# Main.net
KiCad netlist of a schematic drawn in Altium Designer
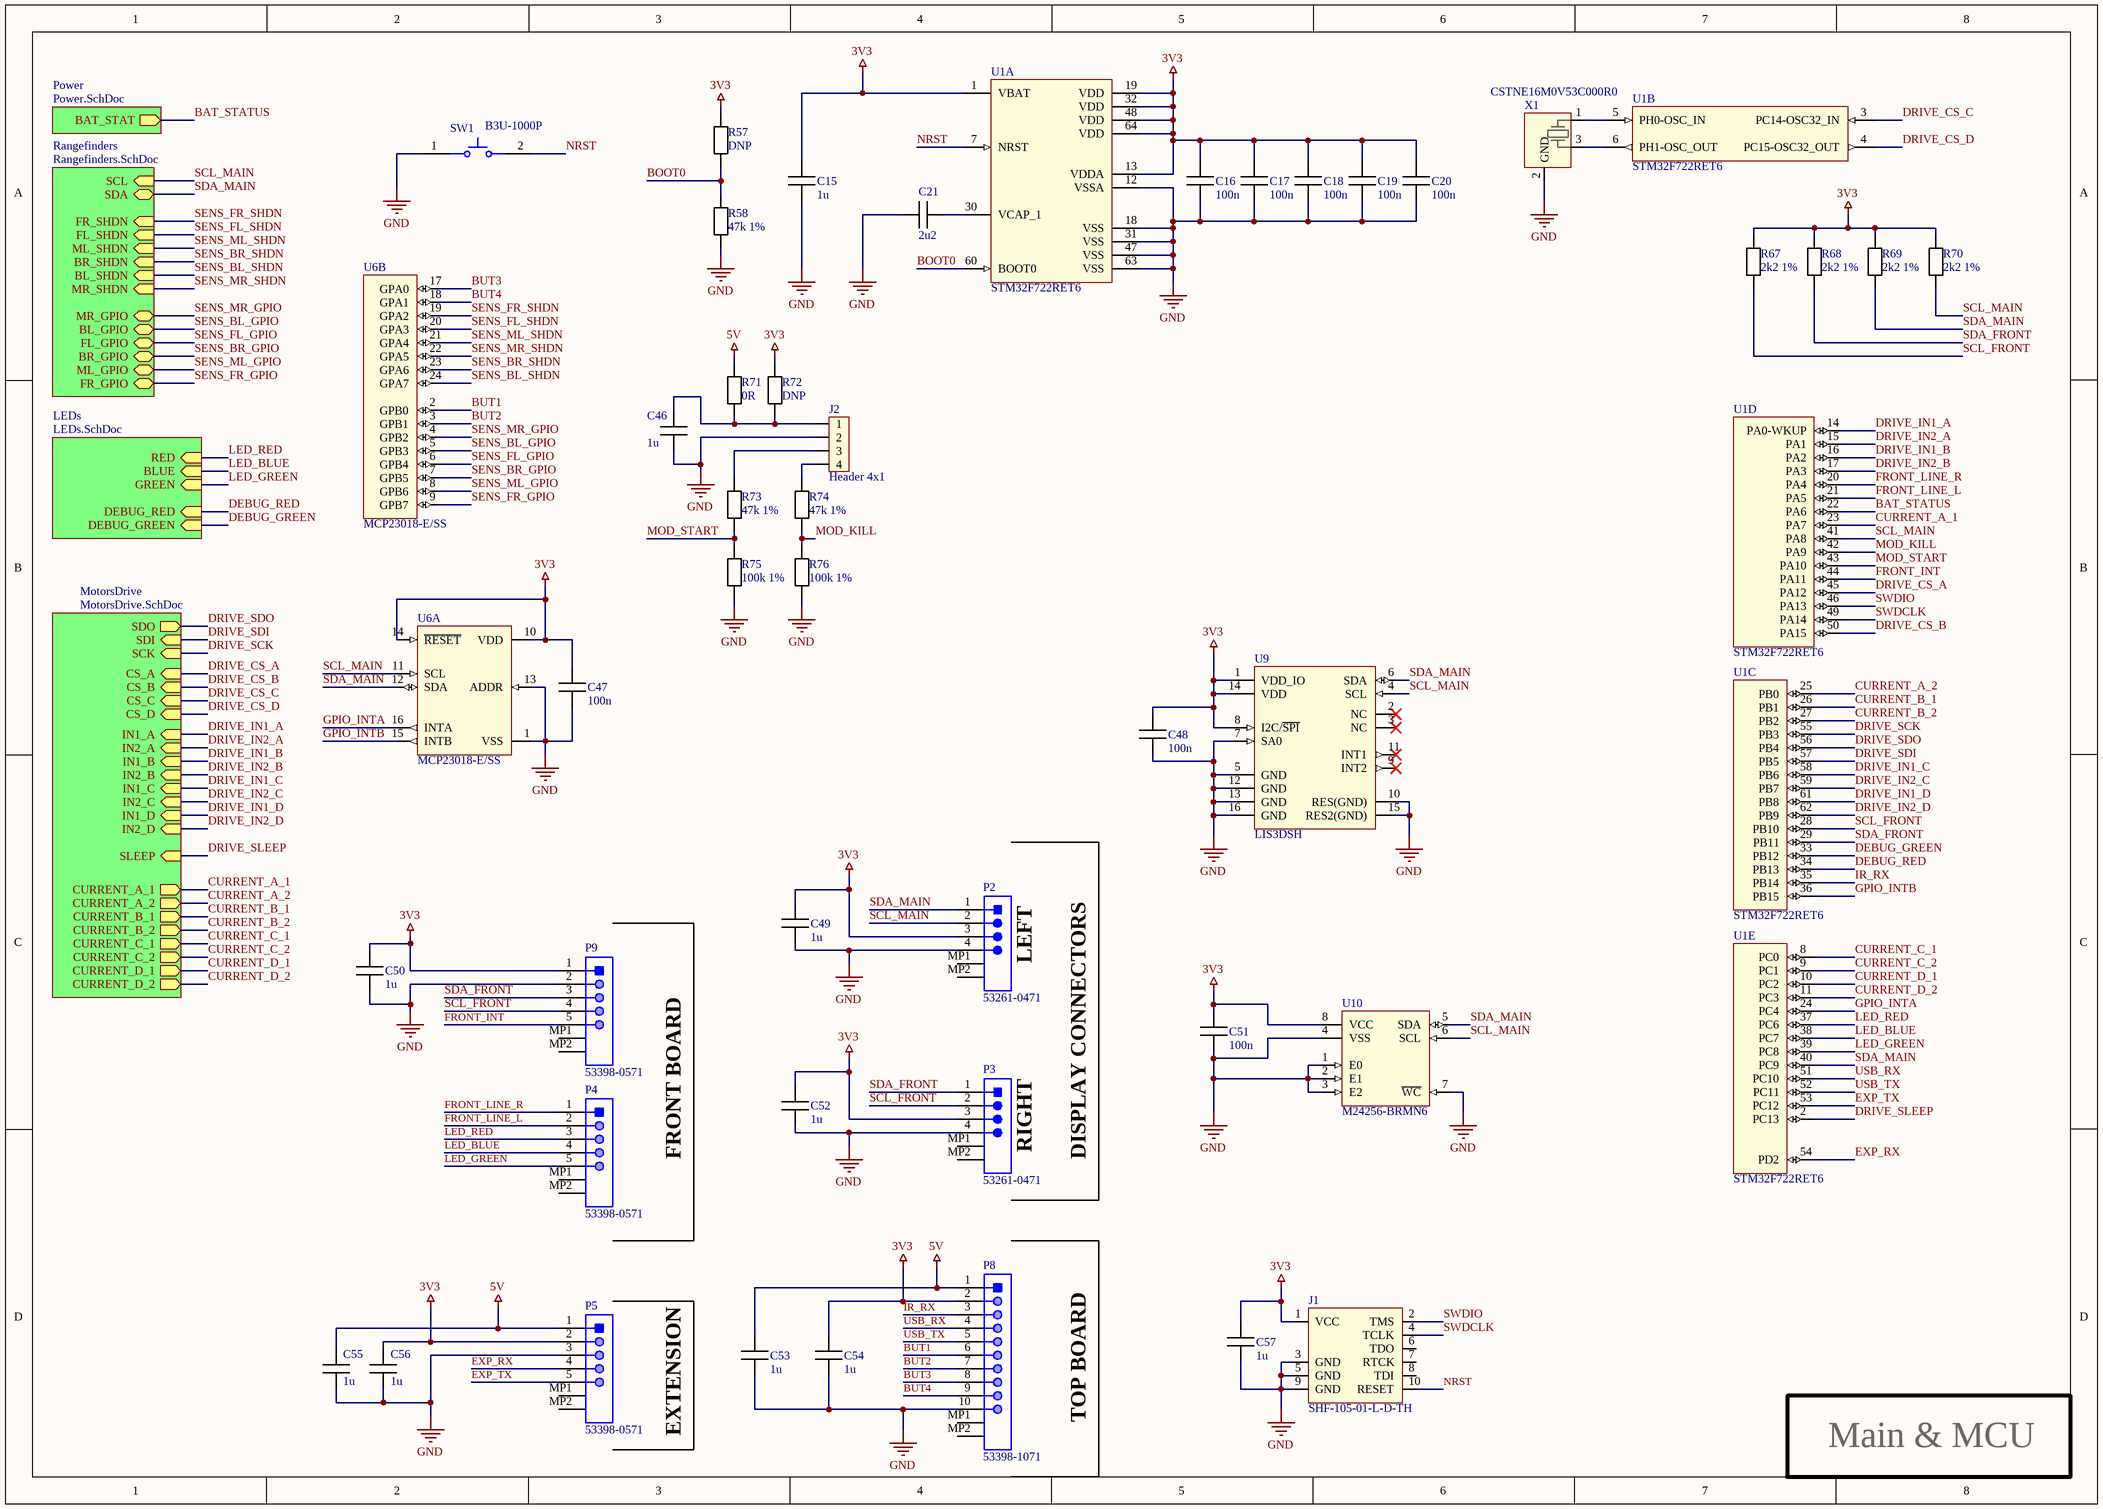
[diagram p0: Main.SchDoc]

(export (version "E")
  (design (tool "Eeschema 10.0.6"))
  (components
    (comp (ref "C15")
      (value "1u")
      (footprint "C_0603_AUTO")
      (fields (field (name "MANUFACTURER") "[Generic]"))
      (libsource (lib "GuowLib") (part "Capacitor"))
    )
    (comp (ref "C16")
      (value "100n")
      (footprint "C_0603_AUTO")
      (fields (field (name "MANUFACTURER") "[Generic]"))
      (libsource (lib "GuowLib") (part "Capacitor"))
    )
    (comp (ref "C17")
      (value "100n")
      (footprint "C_0603_AUTO")
      (fields (field (name "MANUFACTURER") "[Generic]"))
      (libsource (lib "GuowLib") (part "Capacitor"))
    )
    (comp (ref "C18")
      (value "100n")
      (footprint "C_0603_AUTO")
      (fields (field (name "MANUFACTURER") "[Generic]"))
      (libsource (lib "GuowLib") (part "Capacitor"))
    )
    (comp (ref "C19")
      (value "100n")
      (footprint "C_0603_AUTO")
      (fields (field (name "MANUFACTURER") "[Generic]"))
      (libsource (lib "GuowLib") (part "Capacitor"))
    )
    (comp (ref "C20")
      (value "100n")
      (footprint "C_0603_AUTO")
      (fields (field (name "MANUFACTURER") "[Generic]"))
      (libsource (lib "GuowLib") (part "Capacitor"))
    )
    (comp (ref "C21")
      (value "2u2")
      (footprint "C_0603_AUTO")
      (fields (field (name "MANUFACTURER") "[Generic]"))
      (libsource (lib "GuowLib") (part "Capacitor"))
    )
    (comp (ref "C46")
      (value "1u")
      (footprint "C_0603_AUTO")
      (fields (field (name "MANUFACTURER") "[Generic]"))
      (libsource (lib "GuowLib") (part "Capacitor"))
    )
    (comp (ref "C47")
      (value "100n")
      (footprint "C_0603_AUTO")
      (fields (field (name "MANUFACTURER") "[Generic]"))
      (libsource (lib "GuowLib") (part "Capacitor"))
    )
    (comp (ref "C48")
      (value "100n")
      (footprint "C_0603_AUTO")
      (fields (field (name "MANUFACTURER") "[Generic]"))
      (libsource (lib "GuowLib") (part "Capacitor"))
    )
    (comp (ref "C49")
      (value "1u")
      (footprint "C_0603_AUTO")
      (fields (field (name "MANUFACTURER") "[Generic]"))
      (libsource (lib "GuowLib") (part "Capacitor"))
    )
    (comp (ref "C50")
      (value "1u")
      (footprint "C_0603_AUTO")
      (fields (field (name "MANUFACTURER") "[Generic]"))
      (libsource (lib "GuowLib") (part "Capacitor"))
    )
    (comp (ref "C51")
      (value "100n")
      (footprint "C_0603_AUTO")
      (fields (field (name "MANUFACTURER") "[Generic]"))
      (libsource (lib "GuowLib") (part "Capacitor"))
    )
    (comp (ref "C52")
      (value "1u")
      (footprint "C_0603_AUTO")
      (fields (field (name "MANUFACTURER") "[Generic]"))
      (libsource (lib "GuowLib") (part "Capacitor"))
    )
    (comp (ref "C53")
      (value "1u")
      (footprint "C_0603_AUTO")
      (fields (field (name "MANUFACTURER") "[Generic]"))
      (libsource (lib "GuowLib") (part "Capacitor"))
    )
    (comp (ref "C54")
      (value "1u")
      (footprint "C_0603_AUTO")
      (fields (field (name "MANUFACTURER") "[Generic]"))
      (libsource (lib "GuowLib") (part "Capacitor"))
    )
    (comp (ref "C55")
      (value "1u")
      (footprint "C_0603_AUTO")
      (fields (field (name "MANUFACTURER") "[Generic]"))
      (libsource (lib "GuowLib") (part "Capacitor"))
    )
    (comp (ref "C56")
      (value "1u")
      (footprint "C_0603_AUTO")
      (fields (field (name "MANUFACTURER") "[Generic]"))
      (libsource (lib "GuowLib") (part "Capacitor"))
    )
    (comp (ref "C57")
      (value "1u")
      (footprint "C_0603_AUTO")
      (fields (field (name "MANUFACTURER") "[Generic]"))
      (libsource (lib "GuowLib") (part "Capacitor"))
    )
    (comp (ref "J1")
      (value "SHF-105-01-L-D-TH")
      (footprint "SHF-105-01-L-D-TH")
      (description "Standard ARM 20 pin JTAG connector. Angle 90 deg.")
      (fields (field (name "MANUFACTURER") "Samtec"))
      (libsource (lib "GuowLib") (part "JTAG_ARM_MINI_10_PIN"))
    )
    (comp (ref "J2")
      (value "Header 4x1")
      (footprint "F_4X1_254")
      (fields (field (name "MANUFACTURER") "NA"))
      (libsource (lib "GuowLib") (part "Header 4x1"))
    )
    (comp (ref "P2")
      (value "53261-0471")
      (footprint "MOLEX-53261-0471_V")
      (description "Male Header, Pitch 1.25 mm, 1 x 4 Position, Height 3.4 mm, -40 to 85 degC, RoHS, Tape and Reel")
      (fields (field (name "MANUFACTURER") "Molex"))
      (libsource (lib "Altium Content Vault") (part "CN-1P-2M-R4_A"))
    )
    (comp (ref "P3")
      (value "53261-0471")
      (footprint "MOLEX-53261-0471_V")
      (description "Male Header, Pitch 1.25 mm, 1 x 4 Position, Height 3.4 mm, -40 to 85 degC, RoHS, Tape and Reel")
      (fields (field (name "MANUFACTURER") "Molex"))
      (libsource (lib "Altium Content Vault") (part "CN-1P-2M-R4_A"))
    )
    (comp (ref "P4")
      (value "53398-0571")
      (footprint "MOLX-53398-0571-5_V")
      (description "Male Header, Pitch 1.25 mm, 1 x 5 Postion, Height 4.7 mm, -40 to 85 degC, RoHS, Tape and Reel")
      (fields (field (name "MANUFACTURER") "Molex"))
      (libsource (lib "Altium Content Vault") (part "CN-1P-2M-R5"))
    )
    (comp (ref "P5")
      (value "53398-0571")
      (footprint "MOLX-53398-0571-5_V")
      (description "Male Header, Pitch 1.25 mm, 1 x 5 Postion, Height 4.7 mm, -40 to 85 degC, RoHS, Tape and Reel")
      (fields (field (name "MANUFACTURER") "Molex"))
      (libsource (lib "Altium Content Vault") (part "CN-1P-2M-R5"))
    )
    (comp (ref "P8")
      (value "53398-1071")
      (footprint "MOLX-53398-1071_V")
      (description "Male Header, Pitch 1.25 mm, 1 x 10 Position, Height 4.7 mm, -40 to 85 degC, RoHS, Tape and Reel")
      (fields (field (name "MANUFACTURER") "Molex"))
      (libsource (lib "Altium Content Vault") (part "CN-1P-2M-R10"))
    )
    (comp (ref "P9")
      (value "53398-0571")
      (footprint "MOLX-53398-0571-5_V")
      (description "Male Header, Pitch 1.25 mm, 1 x 5 Postion, Height 4.7 mm, -40 to 85 degC, RoHS, Tape and Reel")
      (fields (field (name "MANUFACTURER") "Molex"))
      (libsource (lib "Altium Content Vault") (part "CN-1P-2M-R5"))
    )
    (comp (ref "R57")
      (value "DNP")
      (footprint "R_0603_AUTO")
      (fields (field (name "MPN") "[Generic]"))
      (libsource (lib "GuowLib") (part "Resistor"))
    )
    (comp (ref "R58")
      (value "47k 1%")
      (footprint "R_0603_AUTO")
      (fields (field (name "MPN") "[Generic]"))
      (libsource (lib "GuowLib") (part "Resistor"))
    )
    (comp (ref "R67")
      (value "2k2 1%")
      (footprint "R_0603_AUTO")
      (fields (field (name "MPN") "[Generic]"))
      (libsource (lib "GuowLib") (part "Resistor"))
    )
    (comp (ref "R68")
      (value "2k2 1%")
      (footprint "R_0603_AUTO")
      (fields (field (name "MPN") "[Generic]"))
      (libsource (lib "GuowLib") (part "Resistor"))
    )
    (comp (ref "R69")
      (value "2k2 1%")
      (footprint "R_0603_AUTO")
      (fields (field (name "MPN") "[Generic]"))
      (libsource (lib "GuowLib") (part "Resistor"))
    )
    (comp (ref "R70")
      (value "2k2 1%")
      (footprint "R_0603_AUTO")
      (fields (field (name "MPN") "[Generic]"))
      (libsource (lib "GuowLib") (part "Resistor"))
    )
    (comp (ref "R71")
      (value "0R")
      (footprint "R_0603_AUTO")
      (fields (field (name "MPN") "[Generic]"))
      (libsource (lib "GuowLib") (part "Resistor"))
    )
    (comp (ref "R72")
      (value "DNP")
      (footprint "R_0603_AUTO")
      (fields (field (name "MPN") "[Generic]"))
      (libsource (lib "GuowLib") (part "Resistor"))
    )
    (comp (ref "R73")
      (value "47k 1%")
      (footprint "R_0603_AUTO")
      (fields (field (name "MPN") "[Generic]"))
      (libsource (lib "GuowLib") (part "Resistor"))
    )
    (comp (ref "R74")
      (value "47k 1%")
      (footprint "R_0603_AUTO")
      (fields (field (name "MPN") "[Generic]"))
      (libsource (lib "GuowLib") (part "Resistor"))
    )
    (comp (ref "R75")
      (value "100k 1%")
      (footprint "R_0603_AUTO")
      (fields (field (name "MPN") "[Generic]"))
      (libsource (lib "GuowLib") (part "Resistor"))
    )
    (comp (ref "R76")
      (value "100k 1%")
      (footprint "R_0603_AUTO")
      (fields (field (name "MPN") "[Generic]"))
      (libsource (lib "GuowLib") (part "Resistor"))
    )
    (comp (ref "SW1")
      (value "B3U-1000P")
      (footprint "OMRON-B3U-1000_V")
      (description "Ultra-Small Tactile Switch, 0.05 A, 12 V, -25 to 70 degC, 2-Pin SMD, RoHS, Tape and Reel")
      (fields (field (name "MANUFACTURER") "Omron Electronic Components"))
      (libsource (lib "Altium Content Vault") (part "SW-SPST-NO-2"))
    )
    (comp (ref "U1")
      (value "STM32F722RET6")
      (footprint "LQFP_64_HAND")
      (description "ST 32-bit MCU, 64-pin package")
      (fields (field (name "MANUFACTURER") "STMicroelectronics"))
      (libsource (lib "GuowLib") (part "STM32F722RET6"))
    )
    (comp (ref "U6")
      (value "MCP23018-E/SS")
      (footprint "SSOP-24_HAND")
      (description "Expander I/O, 16-bit, 3.4 MHz, I2C, 1.8 V, 5.5 V, SSOP24")
      (fields (field (name "MANUFACTURER") "Microchip"))
      (libsource (lib "GuowLib") (part "MCP23018-E/SS"))
    )
    (comp (ref "U9")
      (value "LIS3DSH")
      (footprint "LGA16_AUTO")
      (fields (field (name "MANUFACTURER") "STMicroelectronics"))
      (libsource (lib "GuowLib") (part "LIS3DSH"))
    )
    (comp (ref "U10")
      (value "M24256-BRMN6")
      (footprint "SOIC_8_AUTO")
      (description "256 Kbit Serial I2C Bus EEPROM")
      (fields (field (name "MANUFACTURER") "STMicroelectronics"))
      (libsource (lib "GuowLib") (part "M24256-BRMN6"))
    )
    (comp (ref "X1")
      (value "CSTNE16M0V53C000R0")
      (footprint "Murata_CSTCE")
      (description "16MHz crystal resonator")
      (fields (field (name "MANUFACTURER") "Murata"))
      (libsource (lib "GuowLib") (part "CSTNE16M0V53C000R0"))
    )
  )
  (nets
    (net (code "1") (name "/BAT_STATUS") (class "Default")
      (node (ref "U1") (pin "22") (pinfunction "PA6_22") (pintype "bidirectional"))
    )
    (net (code "2") (name "/BOOT0") (class "Default")
      (node (ref "R57") (pin "1") (pinfunction "1_1") (pintype "passive"))
      (node (ref "R58") (pin "2") (pinfunction "2_2") (pintype "passive"))
      (node (ref "U1") (pin "60") (pinfunction "BOOT0_60") (pintype "input"))
    )
    (net (code "3") (name "/BUT1") (class "Default")
      (node (ref "P8") (pin "6") (pinfunction "6_6") (pintype "passive"))
      (node (ref "U6") (pin "2") (pinfunction "GPB0_2") (pintype "bidirectional"))
    )
    (net (code "4") (name "/BUT2") (class "Default")
      (node (ref "P8") (pin "7") (pinfunction "7_7") (pintype "passive"))
      (node (ref "U6") (pin "3") (pinfunction "GPB1_3") (pintype "bidirectional"))
    )
    (net (code "5") (name "/BUT3") (class "Default")
      (node (ref "P8") (pin "8") (pinfunction "8_8") (pintype "passive"))
      (node (ref "U6") (pin "17") (pinfunction "GPA0_17") (pintype "bidirectional"))
    )
    (net (code "6") (name "/BUT4") (class "Default")
      (node (ref "P8") (pin "9") (pinfunction "9_9") (pintype "passive"))
      (node (ref "U6") (pin "18") (pinfunction "GPA1_18") (pintype "bidirectional"))
    )
    (net (code "7") (name "/CURRENT_A_1") (class "Default")
      (node (ref "U1") (pin "23") (pinfunction "PA7_23") (pintype "bidirectional"))
    )
    (net (code "8") (name "/CURRENT_A_2") (class "Default")
      (node (ref "U1") (pin "25") (pinfunction "PB0_25") (pintype "bidirectional"))
    )
    (net (code "9") (name "/CURRENT_B_1") (class "Default")
      (node (ref "U1") (pin "26") (pinfunction "PB1_26") (pintype "bidirectional"))
    )
    (net (code "10") (name "/CURRENT_B_2") (class "Default")
      (node (ref "U1") (pin "27") (pinfunction "PB2_27") (pintype "bidirectional"))
    )
    (net (code "11") (name "/CURRENT_C_1") (class "Default")
      (node (ref "U1") (pin "8") (pinfunction "PC0_8") (pintype "bidirectional"))
    )
    (net (code "12") (name "/CURRENT_C_2") (class "Default")
      (node (ref "U1") (pin "9") (pinfunction "PC1_9") (pintype "bidirectional"))
    )
    (net (code "13") (name "/CURRENT_D_1") (class "Default")
      (node (ref "U1") (pin "10") (pinfunction "PC2_10") (pintype "bidirectional"))
    )
    (net (code "14") (name "/CURRENT_D_2") (class "Default")
      (node (ref "U1") (pin "11") (pinfunction "PC3_11") (pintype "bidirectional"))
    )
    (net (code "15") (name "/DEBUG_GREEN") (class "Default")
      (node (ref "U1") (pin "33") (pinfunction "PB12_33") (pintype "bidirectional"))
    )
    (net (code "16") (name "/DEBUG_RED") (class "Default")
      (node (ref "U1") (pin "34") (pinfunction "PB13_34") (pintype "bidirectional"))
    )
    (net (code "17") (name "/DRIVE_CS_A") (class "Default")
      (node (ref "U1") (pin "45") (pinfunction "PA12_45") (pintype "bidirectional"))
    )
    (net (code "18") (name "/DRIVE_CS_B") (class "Default")
      (node (ref "U1") (pin "50") (pinfunction "PA15_50") (pintype "bidirectional"))
    )
    (net (code "19") (name "/DRIVE_CS_C") (class "Default")
      (node (ref "U1") (pin "3") (pinfunction "PC14-OSC32_IN_3") (pintype "input"))
    )
    (net (code "20") (name "/DRIVE_CS_D") (class "Default")
      (node (ref "U1") (pin "4") (pinfunction "PC15-OSC32_OUT_4") (pintype "output"))
    )
    (net (code "21") (name "/DRIVE_IN1_A") (class "Default")
      (node (ref "U1") (pin "14") (pinfunction "PA0-WKUP_14") (pintype "bidirectional"))
    )
    (net (code "22") (name "/DRIVE_IN1_B") (class "Default")
      (node (ref "U1") (pin "16") (pinfunction "PA2_16") (pintype "bidirectional"))
    )
    (net (code "23") (name "/DRIVE_IN1_C") (class "Default")
      (node (ref "U1") (pin "58") (pinfunction "PB6_58") (pintype "bidirectional"))
    )
    (net (code "24") (name "/DRIVE_IN1_D") (class "Default")
      (node (ref "U1") (pin "61") (pinfunction "PB8_61") (pintype "bidirectional"))
    )
    (net (code "25") (name "/DRIVE_IN2_A") (class "Default")
      (node (ref "U1") (pin "15") (pinfunction "PA1_15") (pintype "bidirectional"))
    )
    (net (code "26") (name "/DRIVE_IN2_B") (class "Default")
      (node (ref "U1") (pin "17") (pinfunction "PA3_17") (pintype "bidirectional"))
    )
    (net (code "27") (name "/DRIVE_IN2_C") (class "Default")
      (node (ref "U1") (pin "59") (pinfunction "PB7_59") (pintype "bidirectional"))
    )
    (net (code "28") (name "/DRIVE_IN2_D") (class "Default")
      (node (ref "U1") (pin "62") (pinfunction "PB9_62") (pintype "bidirectional"))
    )
    (net (code "29") (name "/DRIVE_SCK") (class "Default")
      (node (ref "U1") (pin "55") (pinfunction "PB3_55") (pintype "bidirectional"))
    )
    (net (code "30") (name "/DRIVE_SDI") (class "Default")
      (node (ref "U1") (pin "57") (pinfunction "PB5_57") (pintype "bidirectional"))
    )
    (net (code "31") (name "/DRIVE_SDO") (class "Default")
      (node (ref "U1") (pin "56") (pinfunction "PB4_56") (pintype "bidirectional"))
    )
    (net (code "32") (name "/DRIVE_SLEEP") (class "Default")
      (node (ref "U1") (pin "2") (pinfunction "PC13_2") (pintype "bidirectional"))
    )
    (net (code "33") (name "/EXP_RX") (class "Default")
      (node (ref "P5") (pin "4") (pinfunction "4_4") (pintype "passive"))
      (node (ref "U1") (pin "54") (pinfunction "PD2_54") (pintype "bidirectional"))
    )
    (net (code "34") (name "/EXP_TX") (class "Default")
      (node (ref "P5") (pin "5") (pinfunction "5_5") (pintype "passive"))
      (node (ref "U1") (pin "53") (pinfunction "PC12_53") (pintype "bidirectional"))
    )
    (net (code "35") (name "/FRONT_INT") (class "Default")
      (node (ref "P9") (pin "5") (pinfunction "5_5") (pintype "passive"))
      (node (ref "U1") (pin "44") (pinfunction "PA11_44") (pintype "bidirectional"))
    )
    (net (code "36") (name "/FRONT_LINE_L") (class "Default")
      (node (ref "P4") (pin "2") (pinfunction "2_2") (pintype "passive"))
      (node (ref "U1") (pin "21") (pinfunction "PA5_21") (pintype "bidirectional"))
    )
    (net (code "37") (name "/FRONT_LINE_R") (class "Default")
      (node (ref "P4") (pin "1") (pinfunction "1_1") (pintype "passive"))
      (node (ref "U1") (pin "20") (pinfunction "PA4_20") (pintype "bidirectional"))
    )
    (net (code "38") (name "/GPIO_INTA") (class "Default")
      (node (ref "U1") (pin "24") (pinfunction "PC4_24") (pintype "bidirectional"))
      (node (ref "U6") (pin "16") (pinfunction "INTA_16") (pintype "output"))
    )
    (net (code "39") (name "/GPIO_INTB") (class "Default")
      (node (ref "U1") (pin "36") (pinfunction "PB15_36") (pintype "bidirectional"))
      (node (ref "U6") (pin "15") (pinfunction "INTB_15") (pintype "output"))
    )
    (net (code "40") (name "/IR_RX") (class "Default")
      (node (ref "P8") (pin "3") (pinfunction "3_3") (pintype "passive"))
      (node (ref "U1") (pin "35") (pinfunction "PB14_35") (pintype "bidirectional"))
    )
    (net (code "41") (name "/LED_BLUE") (class "Default")
      (node (ref "P4") (pin "4") (pinfunction "4_4") (pintype "passive"))
      (node (ref "U1") (pin "38") (pinfunction "PC7_38") (pintype "bidirectional"))
    )
    (net (code "42") (name "/LED_GREEN") (class "Default")
      (node (ref "P4") (pin "5") (pinfunction "5_5") (pintype "passive"))
      (node (ref "U1") (pin "39") (pinfunction "PC8_39") (pintype "bidirectional"))
    )
    (net (code "43") (name "/LED_RED") (class "Default")
      (node (ref "P4") (pin "3") (pinfunction "3_3") (pintype "passive"))
      (node (ref "U1") (pin "37") (pinfunction "PC6_37") (pintype "bidirectional"))
    )
    (net (code "44") (name "/MOD_KILL") (class "Default")
      (node (ref "R74") (pin "1") (pinfunction "1_1") (pintype "passive"))
      (node (ref "R76") (pin "2") (pinfunction "2_2") (pintype "passive"))
      (node (ref "U1") (pin "42") (pinfunction "PA9_42") (pintype "bidirectional"))
    )
    (net (code "45") (name "/MOD_START") (class "Default")
      (node (ref "R73") (pin "1") (pinfunction "1_1") (pintype "passive"))
      (node (ref "R75") (pin "2") (pinfunction "2_2") (pintype "passive"))
      (node (ref "U1") (pin "43") (pinfunction "PA10_43") (pintype "bidirectional"))
    )
    (net (code "46") (name "/NRST") (class "Default")
      (node (ref "J1") (pin "10") (pinfunction "RESET_10") (pintype "passive"))
      (node (ref "SW1") (pin "2") (pinfunction "2_2") (pintype "passive"))
      (node (ref "U1") (pin "7") (pinfunction "NRST_7") (pintype "input"))
    )
    (net (code "47") (name "/SCL_FRONT") (class "Default")
      (node (ref "P3") (pin "2") (pinfunction "2_2") (pintype "passive"))
      (node (ref "P9") (pin "4") (pinfunction "4_4") (pintype "passive"))
      (node (ref "R67") (pin "1") (pinfunction "1_1") (pintype "passive"))
      (node (ref "U1") (pin "28") (pinfunction "PB10_28") (pintype "bidirectional"))
    )
    (net (code "48") (name "/SCL_MAIN") (class "Default")
      (node (ref "P2") (pin "2") (pinfunction "2_2") (pintype "passive"))
      (node (ref "R70") (pin "1") (pinfunction "1_1") (pintype "passive"))
      (node (ref "U1") (pin "41") (pinfunction "PA8_41") (pintype "bidirectional"))
      (node (ref "U10") (pin "6") (pinfunction "SCL_6") (pintype "input"))
      (node (ref "U6") (pin "11") (pinfunction "SCL_11") (pintype "input"))
      (node (ref "U9") (pin "4") (pinfunction "SCL_4") (pintype "input"))
    )
    (net (code "49") (name "/SDA_FRONT") (class "Default")
      (node (ref "P3") (pin "1") (pinfunction "1_1") (pintype "passive"))
      (node (ref "P9") (pin "3") (pinfunction "3_3") (pintype "passive"))
      (node (ref "R68") (pin "1") (pinfunction "1_1") (pintype "passive"))
      (node (ref "U1") (pin "29") (pinfunction "PB11_29") (pintype "bidirectional"))
    )
    (net (code "50") (name "/SDA_MAIN") (class "Default")
      (node (ref "P2") (pin "1") (pinfunction "1_1") (pintype "passive"))
      (node (ref "R69") (pin "1") (pinfunction "1_1") (pintype "passive"))
      (node (ref "U1") (pin "40") (pinfunction "PC9_40") (pintype "bidirectional"))
      (node (ref "U10") (pin "5") (pinfunction "SDA_5") (pintype "bidirectional"))
      (node (ref "U6") (pin "12") (pinfunction "SDA_12") (pintype "bidirectional"))
      (node (ref "U9") (pin "6") (pinfunction "SDA_6") (pintype "bidirectional"))
    )
    (net (code "51") (name "/SENS_BL_GPIO") (class "Default")
      (node (ref "U6") (pin "5") (pinfunction "GPB3_5") (pintype "bidirectional"))
    )
    (net (code "52") (name "/SENS_BL_SHDN") (class "Default")
      (node (ref "U6") (pin "24") (pinfunction "GPA7_24") (pintype "bidirectional"))
    )
    (net (code "53") (name "/SENS_BR_GPIO") (class "Default")
      (node (ref "U6") (pin "7") (pinfunction "GPB5_7") (pintype "bidirectional"))
    )
    (net (code "54") (name "/SENS_BR_SHDN") (class "Default")
      (node (ref "U6") (pin "23") (pinfunction "GPA6_23") (pintype "bidirectional"))
    )
    (net (code "55") (name "/SENS_FL_GPIO") (class "Default")
      (node (ref "U6") (pin "6") (pinfunction "GPB4_6") (pintype "bidirectional"))
    )
    (net (code "56") (name "/SENS_FL_SHDN") (class "Default")
      (node (ref "U6") (pin "20") (pinfunction "GPA3_20") (pintype "bidirectional"))
    )
    (net (code "57") (name "/SENS_FR_GPIO") (class "Default")
      (node (ref "U6") (pin "9") (pinfunction "GPB7_9") (pintype "bidirectional"))
    )
    (net (code "58") (name "/SENS_FR_SHDN") (class "Default")
      (node (ref "U6") (pin "19") (pinfunction "GPA2_19") (pintype "bidirectional"))
    )
    (net (code "59") (name "/SENS_ML_GPIO") (class "Default")
      (node (ref "U6") (pin "8") (pinfunction "GPB6_8") (pintype "bidirectional"))
    )
    (net (code "60") (name "/SENS_ML_SHDN") (class "Default")
      (node (ref "U6") (pin "21") (pinfunction "GPA4_21") (pintype "bidirectional"))
    )
    (net (code "61") (name "/SENS_MR_GPIO") (class "Default")
      (node (ref "U6") (pin "4") (pinfunction "GPB2_4") (pintype "bidirectional"))
    )
    (net (code "62") (name "/SENS_MR_SHDN") (class "Default")
      (node (ref "U6") (pin "22") (pinfunction "GPA5_22") (pintype "bidirectional"))
    )
    (net (code "63") (name "/SWDCLK") (class "Default")
      (node (ref "J1") (pin "4") (pinfunction "TCLK_4") (pintype "passive"))
      (node (ref "U1") (pin "49") (pinfunction "PA14_49") (pintype "bidirectional"))
    )
    (net (code "64") (name "/SWDIO") (class "Default")
      (node (ref "J1") (pin "2") (pinfunction "TMS_2") (pintype "passive"))
      (node (ref "U1") (pin "46") (pinfunction "PA13_46") (pintype "bidirectional"))
    )
    (net (code "65") (name "/USB_RX") (class "Default")
      (node (ref "P8") (pin "4") (pinfunction "4_4") (pintype "passive"))
      (node (ref "U1") (pin "51") (pinfunction "PC10_51") (pintype "bidirectional"))
    )
    (net (code "66") (name "/USB_TX") (class "Default")
      (node (ref "P8") (pin "5") (pinfunction "5_5") (pintype "passive"))
      (node (ref "U1") (pin "52") (pinfunction "PC11_52") (pintype "bidirectional"))
    )
    (net (code "67") (name "3V3") (class "Default")
      (node (ref "C15") (pin "2") (pinfunction "2_2") (pintype "passive"))
      (node (ref "C16") (pin "2") (pinfunction "2_2") (pintype "passive"))
      (node (ref "C17") (pin "2") (pinfunction "2_2") (pintype "passive"))
      (node (ref "C18") (pin "2") (pinfunction "2_2") (pintype "passive"))
      (node (ref "C19") (pin "2") (pinfunction "2_2") (pintype "passive"))
      (node (ref "C20") (pin "2") (pinfunction "2_2") (pintype "passive"))
      (node (ref "C47") (pin "2") (pinfunction "2_2") (pintype "passive"))
      (node (ref "C48") (pin "2") (pinfunction "2_2") (pintype "passive"))
      (node (ref "C49") (pin "2") (pinfunction "2_2") (pintype "passive"))
      (node (ref "C50") (pin "2") (pinfunction "2_2") (pintype "passive"))
      (node (ref "C51") (pin "2") (pinfunction "2_2") (pintype "passive"))
      (node (ref "C52") (pin "2") (pinfunction "2_2") (pintype "passive"))
      (node (ref "C54") (pin "2") (pinfunction "2_2") (pintype "passive"))
      (node (ref "C56") (pin "2") (pinfunction "2_2") (pintype "passive"))
      (node (ref "C57") (pin "2") (pinfunction "2_2") (pintype "passive"))
      (node (ref "J1") (pin "1") (pinfunction "VCC_1") (pintype "passive"))
      (node (ref "P2") (pin "3") (pinfunction "3_3") (pintype "passive"))
      (node (ref "P3") (pin "3") (pinfunction "3_3") (pintype "passive"))
      (node (ref "P5") (pin "2") (pinfunction "2_2") (pintype "passive"))
      (node (ref "P8") (pin "2") (pinfunction "2_2") (pintype "passive"))
      (node (ref "P9") (pin "1") (pinfunction "1_1") (pintype "passive"))
      (node (ref "R57") (pin "2") (pinfunction "2_2") (pintype "passive"))
      (node (ref "R67") (pin "2") (pinfunction "2_2") (pintype "passive"))
      (node (ref "R68") (pin "2") (pinfunction "2_2") (pintype "passive"))
      (node (ref "R69") (pin "2") (pinfunction "2_2") (pintype "passive"))
      (node (ref "R70") (pin "2") (pinfunction "2_2") (pintype "passive"))
      (node (ref "R72") (pin "2") (pinfunction "2_2") (pintype "passive"))
      (node (ref "U1") (pin "1") (pinfunction "VBAT_1") (pintype "power_in"))
      (node (ref "U1") (pin "13") (pinfunction "VDDA_13") (pintype "power_in"))
      (node (ref "U1") (pin "19") (pinfunction "VDD_19") (pintype "power_in"))
      (node (ref "U1") (pin "32") (pinfunction "VDD_32") (pintype "power_in"))
      (node (ref "U1") (pin "48") (pinfunction "VDD_48") (pintype "power_in"))
      (node (ref "U1") (pin "64") (pinfunction "VDD_64") (pintype "power_in"))
      (node (ref "U10") (pin "8") (pinfunction "VCC_8") (pintype "power_in"))
      (node (ref "U6") (pin "10") (pinfunction "VDD_10") (pintype "power_in"))
      (node (ref "U6") (pin "14") (pinfunction "~{RESET}_14") (pintype "input"))
      (node (ref "U9") (pin "1") (pinfunction "VDD_IO_1") (pintype "power_in"))
      (node (ref "U9") (pin "14") (pinfunction "VDD_14") (pintype "power_in"))
      (node (ref "U9") (pin "8") (pinfunction "I2C/~{SPI}_8") (pintype "input"))
    )
    (net (code "68") (name "5V") (class "Default")
      (node (ref "C53") (pin "2") (pinfunction "2_2") (pintype "passive"))
      (node (ref "C55") (pin "2") (pinfunction "2_2") (pintype "passive"))
      (node (ref "P5") (pin "1") (pinfunction "1_1") (pintype "passive"))
      (node (ref "P8") (pin "1") (pinfunction "1_1") (pintype "passive"))
      (node (ref "R71") (pin "2") (pinfunction "2_2") (pintype "passive"))
    )
    (net (code "69") (name "GND") (class "Default")
      (node (ref "C15") (pin "1") (pinfunction "1_1") (pintype "passive"))
      (node (ref "C16") (pin "1") (pinfunction "1_1") (pintype "passive"))
      (node (ref "C17") (pin "1") (pinfunction "1_1") (pintype "passive"))
      (node (ref "C18") (pin "1") (pinfunction "1_1") (pintype "passive"))
      (node (ref "C19") (pin "1") (pinfunction "1_1") (pintype "passive"))
      (node (ref "C20") (pin "1") (pinfunction "1_1") (pintype "passive"))
      (node (ref "C21") (pin "2") (pinfunction "2_2") (pintype "passive"))
      (node (ref "C46") (pin "1") (pinfunction "1_1") (pintype "passive"))
      (node (ref "C47") (pin "1") (pinfunction "1_1") (pintype "passive"))
      (node (ref "C48") (pin "1") (pinfunction "1_1") (pintype "passive"))
      (node (ref "C49") (pin "1") (pinfunction "1_1") (pintype "passive"))
      (node (ref "C50") (pin "1") (pinfunction "1_1") (pintype "passive"))
      (node (ref "C51") (pin "1") (pinfunction "1_1") (pintype "passive"))
      (node (ref "C52") (pin "1") (pinfunction "1_1") (pintype "passive"))
      (node (ref "C53") (pin "1") (pinfunction "1_1") (pintype "passive"))
      (node (ref "C54") (pin "1") (pinfunction "1_1") (pintype "passive"))
      (node (ref "C55") (pin "1") (pinfunction "1_1") (pintype "passive"))
      (node (ref "C56") (pin "1") (pinfunction "1_1") (pintype "passive"))
      (node (ref "C57") (pin "1") (pinfunction "1_1") (pintype "passive"))
      (node (ref "J1") (pin "3") (pinfunction "GND_3") (pintype "passive"))
      (node (ref "J1") (pin "5") (pinfunction "GND_5") (pintype "passive"))
      (node (ref "J1") (pin "9") (pinfunction "GND_9") (pintype "passive"))
      (node (ref "J2") (pin "2") (pinfunction "2_2") (pintype "passive"))
      (node (ref "P2") (pin "4") (pinfunction "4_4") (pintype "passive"))
      (node (ref "P3") (pin "4") (pinfunction "4_4") (pintype "passive"))
      (node (ref "P5") (pin "3") (pinfunction "3_3") (pintype "passive"))
      (node (ref "P8") (pin "10") (pinfunction "10_10") (pintype "passive"))
      (node (ref "P9") (pin "2") (pinfunction "2_2") (pintype "passive"))
      (node (ref "R58") (pin "1") (pinfunction "1_1") (pintype "passive"))
      (node (ref "R75") (pin "1") (pinfunction "1_1") (pintype "passive"))
      (node (ref "R76") (pin "1") (pinfunction "1_1") (pintype "passive"))
      (node (ref "SW1") (pin "1") (pinfunction "1_1") (pintype "passive"))
      (node (ref "U1") (pin "12") (pinfunction "VSSA_12") (pintype "power_in"))
      (node (ref "U1") (pin "18") (pinfunction "VSS_18") (pintype "power_in"))
      (node (ref "U1") (pin "31") (pinfunction "VSS_31") (pintype "power_in"))
      (node (ref "U1") (pin "47") (pinfunction "VSS_47") (pintype "power_in"))
      (node (ref "U1") (pin "63") (pinfunction "VSS_63") (pintype "power_in"))
      (node (ref "U10") (pin "1") (pinfunction "E0_1") (pintype "input"))
      (node (ref "U10") (pin "2") (pinfunction "E1_2") (pintype "input"))
      (node (ref "U10") (pin "3") (pinfunction "E2_3") (pintype "input"))
      (node (ref "U10") (pin "4") (pinfunction "VSS_4") (pintype "power_in"))
      (node (ref "U10") (pin "7") (pinfunction "~{WC}_7") (pintype "input"))
      (node (ref "U6") (pin "1") (pinfunction "VSS_1") (pintype "power_in"))
      (node (ref "U6") (pin "13") (pinfunction "ADDR_13") (pintype "input"))
      (node (ref "U9") (pin "10") (pinfunction "RES(GND)_10") (pintype "passive"))
      (node (ref "U9") (pin "12") (pinfunction "GND_12") (pintype "power_in"))
      (node (ref "U9") (pin "13") (pinfunction "GND_13") (pintype "power_in"))
      (node (ref "U9") (pin "15") (pinfunction "RES2(GND)_15") (pintype "passive"))
      (node (ref "U9") (pin "16") (pinfunction "GND_16") (pintype "power_in"))
      (node (ref "U9") (pin "5") (pinfunction "GND_5") (pintype "power_in"))
      (node (ref "U9") (pin "7") (pinfunction "SA0_7") (pintype "input"))
      (node (ref "X1") (pin "2") (pinfunction "GND_2") (pintype "power_in"))
    )
    (net (code "70") (name "Net-(C46-Pad2)") (class "Default")
      (node (ref "C46") (pin "2") (pinfunction "2_2") (pintype "passive"))
      (node (ref "J2") (pin "1") (pinfunction "1_1") (pintype "passive"))
      (node (ref "R71") (pin "1") (pinfunction "1_1") (pintype "passive"))
      (node (ref "R72") (pin "1") (pinfunction "1_1") (pintype "passive"))
    )
    (net (code "71") (name "Net-(J2-Pad3)") (class "Default")
      (node (ref "J2") (pin "3") (pinfunction "3_3") (pintype "passive"))
      (node (ref "R73") (pin "2") (pinfunction "2_2") (pintype "passive"))
    )
    (net (code "72") (name "Net-(J2-Pad4)") (class "Default")
      (node (ref "J2") (pin "4") (pinfunction "4_4") (pintype "passive"))
      (node (ref "R74") (pin "2") (pinfunction "2_2") (pintype "passive"))
    )
    (net (code "73") (name "Net-(U1A-VCAP_1)") (class "Default")
      (node (ref "C21") (pin "1") (pinfunction "1_1") (pintype "passive"))
      (node (ref "U1") (pin "30") (pinfunction "VCAP_1_30") (pintype "passive"))
    )
    (net (code "74") (name "Net-(U1B-PH0-OSC_IN)") (class "Default")
      (node (ref "U1") (pin "5") (pinfunction "PH0-OSC_IN_5") (pintype "input"))
      (node (ref "X1") (pin "1") (pinfunction "1_1") (pintype "passive"))
    )
    (net (code "75") (name "Net-(U1B-PH1-OSC_OUT)") (class "Default")
      (node (ref "U1") (pin "6") (pinfunction "PH1-OSC_OUT_6") (pintype "output"))
      (node (ref "X1") (pin "3") (pinfunction "3_3") (pintype "passive"))
    )
    (net (code "76") (name "unconnected-(J1-RTCK-Pad7)") (class "Default")
      (node (ref "J1") (pin "7") (pinfunction "RTCK_7") (pintype "passive"))
    )
    (net (code "77") (name "unconnected-(J1-TDI-Pad8)") (class "Default")
      (node (ref "J1") (pin "8") (pinfunction "TDI_8") (pintype "passive"))
    )
    (net (code "78") (name "unconnected-(J1-TDO-Pad6)") (class "Default")
      (node (ref "J1") (pin "6") (pinfunction "TDO_6") (pintype "passive"))
    )
    (net (code "79") (name "unconnected-(P2-PadMP1)") (class "Default")
      (node (ref "P2") (pin "MP1") (pinfunction "MP1_MP1") (pintype "passive"))
    )
    (net (code "80") (name "unconnected-(P2-PadMP2)") (class "Default")
      (node (ref "P2") (pin "MP2") (pinfunction "MP2_MP2") (pintype "passive"))
    )
    (net (code "81") (name "unconnected-(P3-PadMP1)") (class "Default")
      (node (ref "P3") (pin "MP1") (pinfunction "MP1_MP1") (pintype "passive"))
    )
    (net (code "82") (name "unconnected-(P3-PadMP2)") (class "Default")
      (node (ref "P3") (pin "MP2") (pinfunction "MP2_MP2") (pintype "passive"))
    )
    (net (code "83") (name "unconnected-(P4-PadMP1)") (class "Default")
      (node (ref "P4") (pin "MP1") (pinfunction "MP1_MP1") (pintype "passive"))
    )
    (net (code "84") (name "unconnected-(P4-PadMP2)") (class "Default")
      (node (ref "P4") (pin "MP2") (pinfunction "MP2_MP2") (pintype "passive"))
    )
    (net (code "85") (name "unconnected-(P5-PadMP1)") (class "Default")
      (node (ref "P5") (pin "MP1") (pinfunction "MP1_MP1") (pintype "passive"))
    )
    (net (code "86") (name "unconnected-(P5-PadMP2)") (class "Default")
      (node (ref "P5") (pin "MP2") (pinfunction "MP2_MP2") (pintype "passive"))
    )
    (net (code "87") (name "unconnected-(P8-PadMP1)") (class "Default")
      (node (ref "P8") (pin "MP1") (pinfunction "MP1_MP1") (pintype "passive"))
    )
    (net (code "88") (name "unconnected-(P8-PadMP2)") (class "Default")
      (node (ref "P8") (pin "MP2") (pinfunction "MP2_MP2") (pintype "passive"))
    )
    (net (code "89") (name "unconnected-(P9-PadMP1)") (class "Default")
      (node (ref "P9") (pin "MP1") (pinfunction "MP1_MP1") (pintype "passive"))
    )
    (net (code "90") (name "unconnected-(P9-PadMP2)") (class "Default")
      (node (ref "P9") (pin "MP2") (pinfunction "MP2_MP2") (pintype "passive"))
    )
    (net (code "91") (name "unconnected-(U9-INT1-Pad11)") (class "Default")
      (node (ref "U9") (pin "11") (pinfunction "INT1_11") (pintype "output+no_connect"))
    )
    (net (code "92") (name "unconnected-(U9-INT2-Pad9)") (class "Default")
      (node (ref "U9") (pin "9") (pinfunction "INT2_9") (pintype "output+no_connect"))
    )
    (net (code "93") (name "unconnected-(U9-NC-Pad2)") (class "Default")
      (node (ref "U9") (pin "2") (pinfunction "NC_2") (pintype "passive+no_connect"))
    )
    (net (code "94") (name "unconnected-(U9-NC-Pad3)") (class "Default")
      (node (ref "U9") (pin "3") (pinfunction "NC_3") (pintype "passive+no_connect"))
    )
  )
)
